# LEDs.net
KiCad netlist of a schematic drawn in Altium Designer
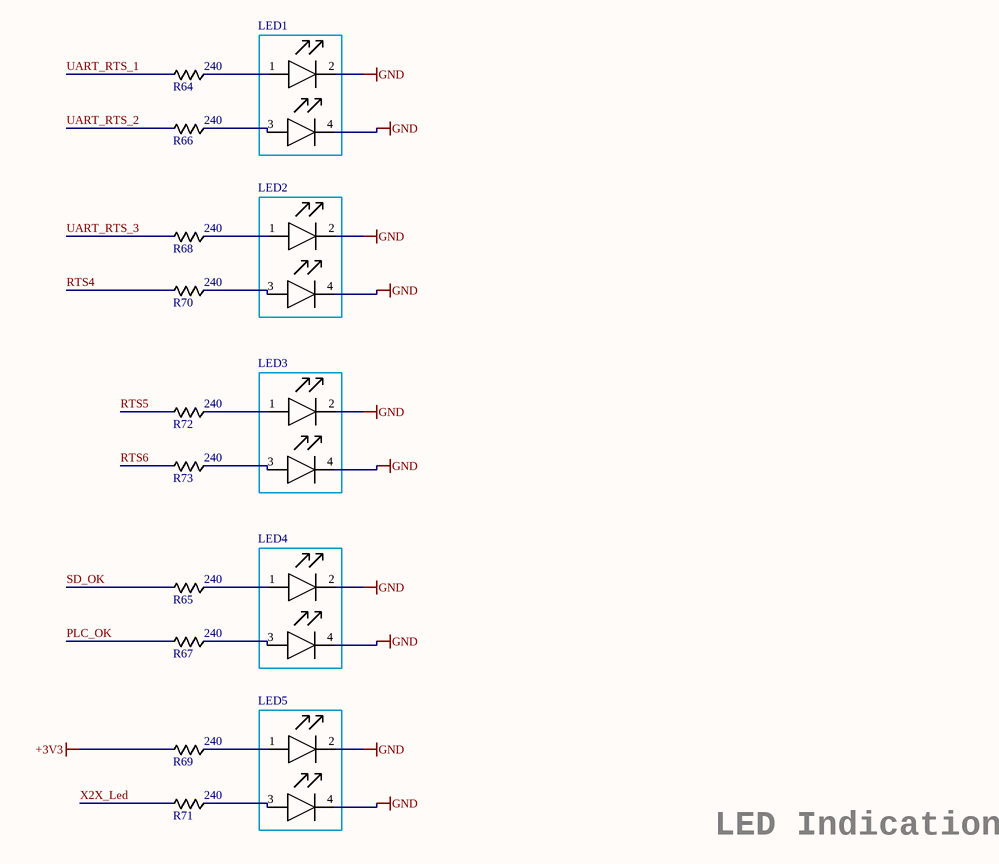
[diagram p0: LEDs.SchDoc]

(export (version "E")
  (design (tool "Eeschema 10.0.6"))
  (components
    (comp (ref "LED1")
      (value "Light Guide 2")
      (footprint "LED SMD DayLight")
      (description "KP-1608SYC")
      (libsource (lib "kontr") (part "Light Guide 2"))
    )
    (comp (ref "LED2")
      (value "Light Guide 2")
      (footprint "LED SMD DayLight")
      (description "KP-1608SYC")
      (libsource (lib "kontr") (part "Light Guide 2"))
    )
    (comp (ref "LED3")
      (value "Light Guide 2")
      (footprint "LED SMD DayLight")
      (description "KP-1608SYC")
      (libsource (lib "kontr") (part "Light Guide 2"))
    )
    (comp (ref "LED4")
      (value "Light Guide 2")
      (footprint "LED SMD DayLight")
      (description "KP-1608SGC")
      (libsource (lib "kontr") (part "Light Guide 2"))
    )
    (comp (ref "LED5")
      (value "Light Guide 2")
      (footprint "LED SMD DayLight")
      (description "KP-1608SGC")
      (libsource (lib "kontr") (part "Light Guide 2"))
    )
    (comp (ref "R64")
      (value "240")
      (footprint "0603 - RES")
      (description "0805 SMD Resistor")
      (libsource (lib "kontr") (part "Resistor 0805"))
    )
    (comp (ref "R65")
      (value "240")
      (footprint "0603 - RES")
      (description "0805 SMD Resistor")
      (libsource (lib "kontr") (part "Resistor 0805"))
    )
    (comp (ref "R66")
      (value "240")
      (footprint "0603 - RES")
      (description "0805 SMD Resistor")
      (libsource (lib "kontr") (part "Resistor 0805"))
    )
    (comp (ref "R67")
      (value "240")
      (footprint "0603 - RES")
      (description "0805 SMD Resistor")
      (libsource (lib "kontr") (part "Resistor 0805"))
    )
    (comp (ref "R68")
      (value "240")
      (footprint "0603 - RES")
      (description "0805 SMD Resistor")
      (libsource (lib "kontr") (part "Resistor 0805"))
    )
    (comp (ref "R69")
      (value "240")
      (footprint "0603 - RES")
      (description "0805 SMD Resistor")
      (libsource (lib "kontr") (part "Resistor 0805"))
    )
    (comp (ref "R70")
      (value "240")
      (footprint "0603 - RES")
      (description "0805 SMD Resistor")
      (libsource (lib "kontr") (part "Resistor 0805"))
    )
    (comp (ref "R71")
      (value "240")
      (footprint "0603 - RES")
      (description "0805 SMD Resistor")
      (libsource (lib "kontr") (part "Resistor 0805"))
    )
    (comp (ref "R72")
      (value "240")
      (footprint "0603 - RES")
      (description "0805 SMD Resistor")
      (libsource (lib "kontr") (part "Resistor 0805"))
    )
    (comp (ref "R73")
      (value "240")
      (footprint "0603 - RES")
      (description "0805 SMD Resistor")
      (libsource (lib "kontr") (part "Resistor 0805"))
    )
  )
  (nets
    (net (code "1") (name "+3V3") (class "Default") (node (ref "R69") (pin "2") (pintype "passive")))
    (net (code "2") (name "/PLC_OK") (class "Default") (node (ref "R67") (pin "2") (pintype "passive")))
    (net (code "3") (name "/RTS4") (class "Default") (node (ref "R70") (pin "2") (pintype "passive")))
    (net (code "4") (name "/RTS5") (class "Default") (node (ref "R72") (pin "2") (pintype "passive")))
    (net (code "5") (name "/RTS6") (class "Default") (node (ref "R73") (pin "2") (pintype "passive")))
    (net (code "6") (name "/SD_OK") (class "Default") (node (ref "R65") (pin "2") (pintype "passive")))
    (net (code "7") (name "/UART_RTS_1") (class "Default") (node (ref "R64") (pin "2") (pintype "passive")))
    (net (code "8") (name "/UART_RTS_2") (class "Default") (node (ref "R66") (pin "2") (pintype "passive")))
    (net (code "9") (name "/UART_RTS_3") (class "Default") (node (ref "R68") (pin "2") (pintype "passive")))
    (net (code "10") (name "/X2X_Led") (class "Default") (node (ref "R71") (pin "2") (pintype "passive")))
    (net (code "11") (name "GND") (class "Default")
      (node (ref "LED1") (pin "2") (pintype "passive"))
      (node (ref "LED1") (pin "4") (pintype "passive"))
      (node (ref "LED2") (pin "2") (pintype "passive"))
      (node (ref "LED2") (pin "4") (pintype "passive"))
      (node (ref "LED3") (pin "2") (pintype "passive"))
      (node (ref "LED3") (pin "4") (pintype "passive"))
      (node (ref "LED4") (pin "2") (pintype "passive"))
      (node (ref "LED4") (pin "4") (pintype "passive"))
      (node (ref "LED5") (pin "2") (pintype "passive"))
      (node (ref "LED5") (pin "4") (pintype "passive"))
    )
    (net (code "12") (name "Net-(LED1-Pad1)") (class "Default")
      (node (ref "LED1") (pin "1") (pintype "passive"))
      (node (ref "R64") (pin "1") (pintype "passive"))
    )
    (net (code "13") (name "Net-(LED1-Pad3)") (class "Default")
      (node (ref "LED1") (pin "3") (pinfunction "3_3") (pintype "passive"))
      (node (ref "R66") (pin "1") (pintype "passive"))
    )
    (net (code "14") (name "Net-(LED2-Pad1)") (class "Default")
      (node (ref "LED2") (pin "1") (pintype "passive"))
      (node (ref "R68") (pin "1") (pintype "passive"))
    )
    (net (code "15") (name "Net-(LED2-Pad3)") (class "Default")
      (node (ref "LED2") (pin "3") (pinfunction "3_3") (pintype "passive"))
      (node (ref "R70") (pin "1") (pintype "passive"))
    )
    (net (code "16") (name "Net-(LED3-Pad1)") (class "Default")
      (node (ref "LED3") (pin "1") (pintype "passive"))
      (node (ref "R72") (pin "1") (pintype "passive"))
    )
    (net (code "17") (name "Net-(LED3-Pad3)") (class "Default")
      (node (ref "LED3") (pin "3") (pinfunction "3_3") (pintype "passive"))
      (node (ref "R73") (pin "1") (pintype "passive"))
    )
    (net (code "18") (name "Net-(LED4-Pad1)") (class "Default")
      (node (ref "LED4") (pin "1") (pintype "passive"))
      (node (ref "R65") (pin "1") (pintype "passive"))
    )
    (net (code "19") (name "Net-(LED4-Pad3)") (class "Default")
      (node (ref "LED4") (pin "3") (pinfunction "3_3") (pintype "passive"))
      (node (ref "R67") (pin "1") (pintype "passive"))
    )
    (net (code "20") (name "Net-(LED5-Pad1)") (class "Default")
      (node (ref "LED5") (pin "1") (pintype "passive"))
      (node (ref "R69") (pin "1") (pintype "passive"))
    )
    (net (code "21") (name "Net-(LED5-Pad3)") (class "Default")
      (node (ref "LED5") (pin "3") (pinfunction "3_3") (pintype "passive"))
      (node (ref "R71") (pin "1") (pintype "passive"))
    )
  )
)
